# CATS-Vega-MCU.net
KiCad netlist of a schematic drawn in Altium Designer
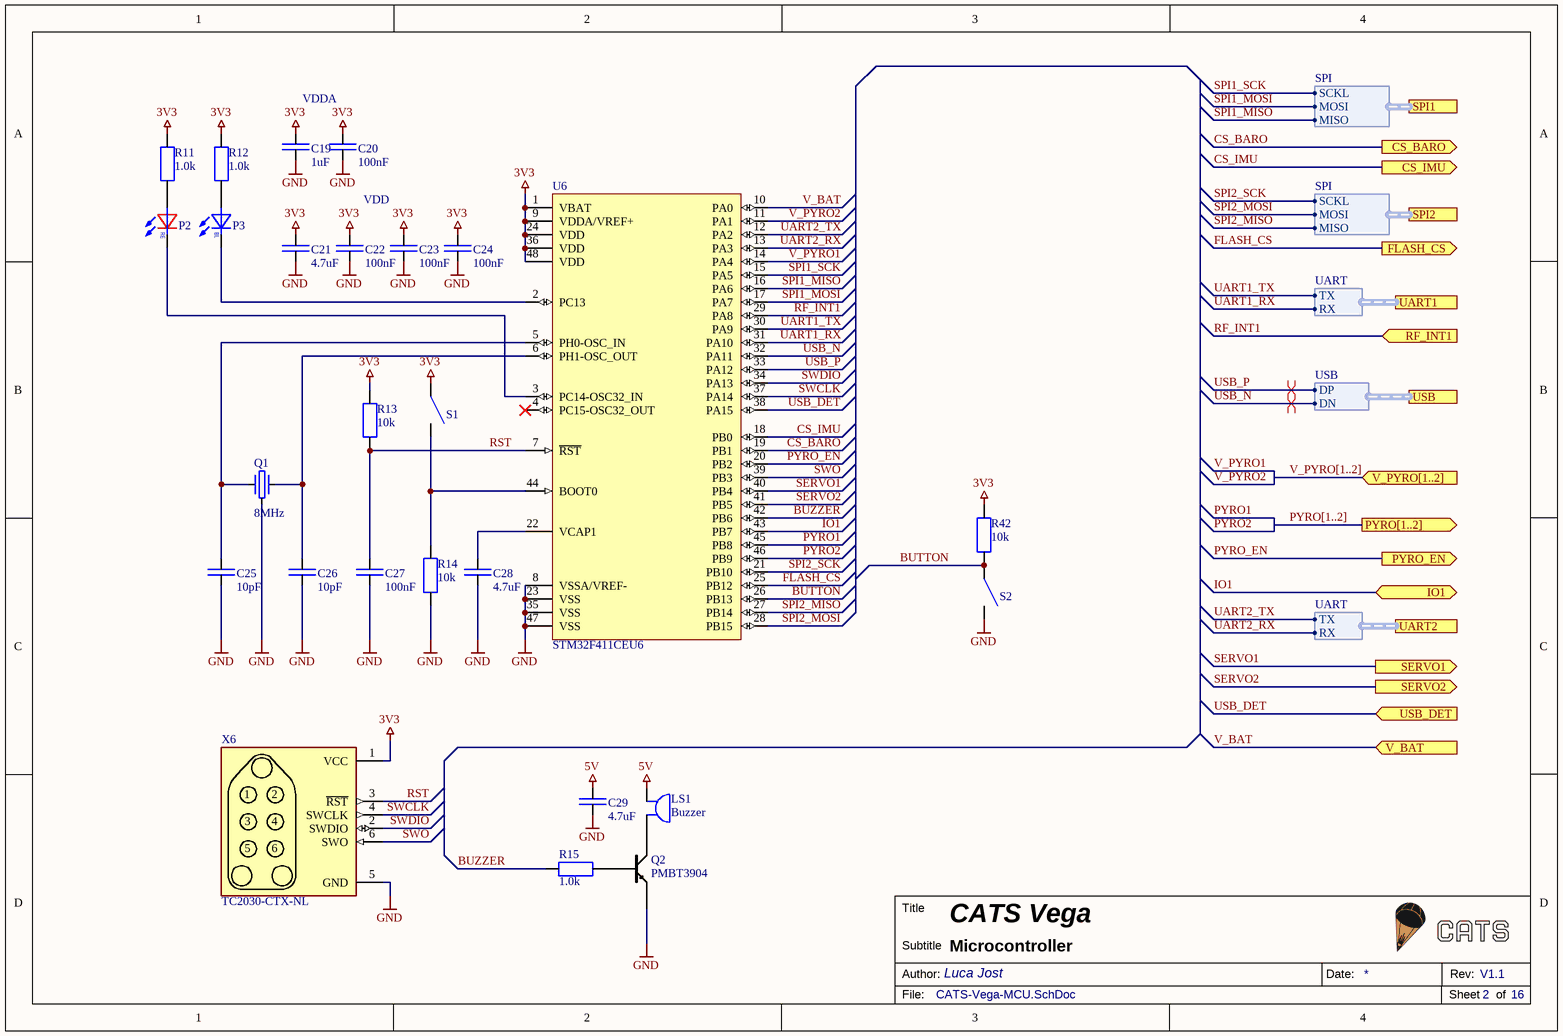
[diagram p0: CATS-Vega-MCU.SchDoc]

(export (version "E")
  (design (tool "Eeschema 10.0.6"))
  (components
    (comp (ref "C19")
      (value "1uF")
      (footprint "SMD Keramikkondensator 0603")
      (description "SMD Ceramic Capacitor E6")
      (libsource (lib "CATS-EUROC") (part "E6 - 1uF"))
    )
    (comp (ref "C20")
      (value "100nF")
      (footprint "SMD Keramikkondensator 0603")
      (description "SMD Ceramic Capacitor E6")
      (libsource (lib "CATS-EUROC") (part "E6 - 100nF"))
    )
    (comp (ref "C21")
      (value "4.7uF")
      (footprint "SMD Keramikkondensator 0603")
      (description "SMD Ceramic Capacitor E6")
      (libsource (lib "CATS-EUROC") (part "E6 - 4.7uF"))
    )
    (comp (ref "C22")
      (value "100nF")
      (footprint "SMD Keramikkondensator 0603")
      (description "SMD Ceramic Capacitor E6")
      (libsource (lib "CATS-EUROC") (part "E6 - 100nF"))
    )
    (comp (ref "C23")
      (value "100nF")
      (footprint "SMD Keramikkondensator 0603")
      (description "SMD Ceramic Capacitor E6")
      (libsource (lib "CATS-EUROC") (part "E6 - 100nF"))
    )
    (comp (ref "C24")
      (value "100nF")
      (footprint "SMD Keramikkondensator 0603")
      (description "SMD Ceramic Capacitor E6")
      (libsource (lib "CATS-EUROC") (part "E6 - 100nF"))
    )
    (comp (ref "C25")
      (value "10pF")
      (footprint "SMD Keramikkondensator 0603")
      (description "SMD Ceramic Capacitor E6")
      (libsource (lib "CATS-EUROC") (part "E6 - 10pF"))
    )
    (comp (ref "C26")
      (value "10pF")
      (footprint "SMD Keramikkondensator 0603")
      (description "SMD Ceramic Capacitor E6")
      (libsource (lib "CATS-EUROC") (part "E6 - 10pF"))
    )
    (comp (ref "C27")
      (value "100nF")
      (footprint "SMD Keramikkondensator 0603")
      (description "SMD Ceramic Capacitor E6")
      (libsource (lib "CATS-EUROC") (part "E6 - 100nF"))
    )
    (comp (ref "C28")
      (value "4.7uF")
      (footprint "SMD Keramikkondensator 0603")
      (description "SMD Ceramic Capacitor E6")
      (libsource (lib "CATS-EUROC") (part "E6 - 4.7uF"))
    )
    (comp (ref "C29")
      (value "4.7uF")
      (footprint "SMD Keramikkondensator 0603")
      (description "SMD Ceramic Capacitor E6")
      (libsource (lib "CATS-EUROC") (part "E6 - 4.7uF"))
    )
    (comp (ref "LS1")
      (value "Buzzer")
      (footprint "SMD BUZZER CMT-8504")
      (description "Buzzers Indicator, Internally Driven Piezo 12V 10mA 3kHz 100dB @ 12V, 10cm Through Hole PC Pins")
      (libsource (lib "Other") (part "Buzzer"))
    )
    (comp (ref "P2")
      (value "LED")
      (footprint "SMD LED 0603")
      (description "Color LED")
      (libsource (lib "") (part "LED_1"))
    )
    (comp (ref "P3")
      (value "LED")
      (footprint "SMD LED 0603")
      (description "Color LED")
      (libsource (lib "Diodes") (part "LED"))
    )
    (comp (ref "Q1")
      (value "8MHz")
      (footprint "SMD Crystal 3.2X2.5X0.8")
      (description "SMD Crystal Resonators 8MHz ±10ppm SMD,3.2x2.5mm")
      (libsource (lib "Other") (part "Crystal"))
    )
    (comp (ref "Q2")
      (value "PMBT3904")
      (footprint "SMD Transistor SOT-23")
      (description "40 V, 200 mA NPN switching transisto")
      (libsource (lib "Electronic Switches") (part "PMBT3904"))
    )
    (comp (ref "R11")
      (value "1.0k")
      (footprint "SMD Widerstand 0603")
      (description "SMD Chip Resistor E24")
      (libsource (lib "CATS-EUROC") (part "E24 - 1.0k"))
    )
    (comp (ref "R12")
      (value "1.0k")
      (footprint "SMD Widerstand 0603")
      (description "SMD Chip Resistor E24")
      (libsource (lib "CATS-EUROC") (part "E24 - 1.0k"))
    )
    (comp (ref "R13")
      (value "10k")
      (footprint "SMD Widerstand 0603")
      (description "SMD Chip Resistor E24")
      (libsource (lib "CATS-EUROC") (part "E24 - 10k"))
    )
    (comp (ref "R14")
      (value "10k")
      (footprint "SMD Widerstand 0603")
      (description "SMD Chip Resistor E24")
      (libsource (lib "CATS-EUROC") (part "E24 - 10k"))
    )
    (comp (ref "R15")
      (value "1.0k")
      (footprint "SMD Widerstand 0603")
      (description "SMD Chip Resistor E24")
      (libsource (lib "") (part "E24 - 1.0k_1"))
    )
    (comp (ref "R42")
      (value "10k")
      (footprint "SMD Widerstand 0603")
      (description "SMD Chip Resistor E24")
      (libsource (lib "CATS-EUROC") (part "E24 - 10k"))
    )
    (comp (ref "S1")
      (value "SMD-Button")
      (footprint "SMD Button 2.5x3x1.2")
      (description "Button SPST")
      (libsource (lib "CATS-EUROC") (part "Button 3mmx2.5mm"))
    )
    (comp (ref "S2")
      (value "SMD-Button")
      (footprint "SMD Button 2.5x3x1.2")
      (description "Button SPST")
      (libsource (lib "CATS-EUROC") (part "Button 3mmx2.5mm"))
    )
    (comp (ref "U6")
      (value "STM32F411CEU6")
      (footprint "SMD IC QFN-48")
      (description "ARM® Cortex®-M4 series Microcontroller IC 32-Bit 100MHz 512KB (512K x 8) FLASH 48-UFQFPN (7x7)")
      (libsource (lib "Microcontrollers") (part "STM32F411CEU6"))
    )
    (comp (ref "X6")
      (value "TC2030-CTX-NL")
      (footprint "SMD Connector TC2030")
      (description "Tag-Connect for ARM-Cortex (6-Pin)")
      (libsource (lib "Connectors") (part "TC2030-CTX-NL"))
    )
  )
  (nets
    (net (code "4") (name "/BUTTON") (class "Default")
      (node (ref "R42") (pin "1") (pinfunction "1_1") (pintype "passive"))
      (node (ref "S2") (pin "1") (pinfunction "1_1") (pintype "passive"))
      (node (ref "U6") (pin "26") (pinfunction "PB13_26") (pintype "bidirectional"))
    )
    (net (code "5") (name "/BUZZER") (class "Default")
      (node (ref "R15") (pin "2") (pinfunction "2_2") (pintype "passive"))
      (node (ref "U6") (pin "42") (pinfunction "PB6_42") (pintype "bidirectional"))
    )
    (net (code "6") (name "/CS_BARO") (class "Default")
      (node (ref "U6") (pin "19") (pinfunction "PB1_19") (pintype "bidirectional"))
    )
    (net (code "7") (name "/CS_IMU") (class "Default")
      (node (ref "U6") (pin "18") (pinfunction "PB0_18") (pintype "bidirectional"))
    )
    (net (code "8") (name "/FLASH_CS") (class "Default")
      (node (ref "U6") (pin "25") (pinfunction "PB12_25") (pintype "bidirectional"))
    )
    (net (code "9") (name "/IO1") (class "Default")
      (node (ref "U6") (pin "43") (pinfunction "PB7_43") (pintype "bidirectional"))
    )
    (net (code "10") (name "/PYRO1") (class "Default")
      (node (ref "U6") (pin "45") (pinfunction "PB8_45") (pintype "bidirectional"))
    )
    (net (code "11") (name "/PYRO2") (class "Default")
      (node (ref "U6") (pin "46") (pinfunction "PB9_46") (pintype "bidirectional"))
    )
    (net (code "13") (name "/PYRO_EN") (class "Default")
      (node (ref "U6") (pin "20") (pinfunction "PB2_20") (pintype "bidirectional"))
    )
    (net (code "14") (name "/RF_INT1") (class "Default")
      (node (ref "U6") (pin "29") (pinfunction "PA8_29") (pintype "bidirectional"))
    )
    (net (code "15") (name "/RST") (class "Default")
      (node (ref "C27") (pin "2") (pinfunction "2_2") (pintype "passive"))
      (node (ref "R13") (pin "1") (pinfunction "1_1") (pintype "passive"))
      (node (ref "U6") (pin "7") (pinfunction "~{RST}_7") (pintype "input"))
      (node (ref "X6") (pin "3") (pinfunction "~{RST}_3") (pintype "output"))
    )
    (net (code "16") (name "/SERVO1") (class "Default")
      (node (ref "U6") (pin "40") (pinfunction "PB4_40") (pintype "bidirectional"))
    )
    (net (code "17") (name "/SERVO2") (class "Default")
      (node (ref "U6") (pin "41") (pinfunction "PB5_41") (pintype "bidirectional"))
    )
    (net (code "18") (name "/SPI1_MISO") (class "Default")
      (node (ref "U6") (pin "16") (pinfunction "PA6_16") (pintype "bidirectional"))
    )
    (net (code "19") (name "/SPI1_MOSI") (class "Default")
      (node (ref "U6") (pin "17") (pinfunction "PA7_17") (pintype "bidirectional"))
    )
    (net (code "20") (name "/SPI1_SCK") (class "Default")
      (node (ref "U6") (pin "15") (pinfunction "PA5_15") (pintype "bidirectional"))
    )
    (net (code "21") (name "/SPI2_MISO") (class "Default")
      (node (ref "U6") (pin "27") (pinfunction "PB14_27") (pintype "bidirectional"))
    )
    (net (code "22") (name "/SPI2_MOSI") (class "Default")
      (node (ref "U6") (pin "28") (pinfunction "PB15_28") (pintype "bidirectional"))
    )
    (net (code "23") (name "/SPI2_SCK") (class "Default")
      (node (ref "U6") (pin "21") (pinfunction "PB10_21") (pintype "bidirectional"))
    )
    (net (code "24") (name "/SWCLK") (class "Default")
      (node (ref "U6") (pin "37") (pinfunction "PA14_37") (pintype "bidirectional"))
      (node (ref "X6") (pin "4") (pinfunction "SWCLK_4") (pintype "output"))
    )
    (net (code "25") (name "/SWDIO") (class "Default")
      (node (ref "U6") (pin "34") (pinfunction "PA13_34") (pintype "bidirectional"))
      (node (ref "X6") (pin "2") (pinfunction "SWDIO_2") (pintype "bidirectional"))
    )
    (net (code "26") (name "/SWO") (class "Default")
      (node (ref "U6") (pin "39") (pinfunction "PB3_39") (pintype "bidirectional"))
      (node (ref "X6") (pin "6") (pinfunction "SWO_6") (pintype "input"))
    )
    (net (code "27") (name "/UART1_RX") (class "Default")
      (node (ref "U6") (pin "31") (pinfunction "PA10_31") (pintype "bidirectional"))
    )
    (net (code "28") (name "/UART1_TX") (class "Default")
      (node (ref "U6") (pin "30") (pinfunction "PA9_30") (pintype "bidirectional"))
    )
    (net (code "29") (name "/UART2_RX") (class "Default")
      (node (ref "U6") (pin "13") (pinfunction "PA3_13") (pintype "bidirectional"))
    )
    (net (code "30") (name "/UART2_TX") (class "Default")
      (node (ref "U6") (pin "12") (pinfunction "PA2_12") (pintype "bidirectional"))
    )
    (net (code "31") (name "/USB_DET") (class "Default")
      (node (ref "U6") (pin "38") (pinfunction "PA15_38") (pintype "bidirectional"))
    )
    (net (code "32") (name "/USB_N") (class "Default")
      (node (ref "U6") (pin "32") (pinfunction "PA11_32") (pintype "bidirectional"))
    )
    (net (code "33") (name "/USB_P") (class "Default")
      (node (ref "U6") (pin "33") (pinfunction "PA12_33") (pintype "bidirectional"))
    )
    (net (code "34") (name "/V_BAT") (class "Default")
      (node (ref "U6") (pin "10") (pinfunction "PA0_10") (pintype "bidirectional"))
    )
    (net (code "35") (name "/V_PYRO1") (class "Default")
      (node (ref "U6") (pin "14") (pinfunction "PA4_14") (pintype "bidirectional"))
    )
    (net (code "36") (name "/V_PYRO2") (class "Default")
      (node (ref "U6") (pin "11") (pinfunction "PA1_11") (pintype "bidirectional"))
    )
    (net (code "41") (name "3V3") (class "Default")
      (node (ref "C19") (pin "2") (pinfunction "2_2") (pintype "passive"))
      (node (ref "C20") (pin "2") (pinfunction "2_2") (pintype "passive"))
      (node (ref "C21") (pin "2") (pinfunction "2_2") (pintype "passive"))
      (node (ref "C22") (pin "2") (pinfunction "2_2") (pintype "passive"))
      (node (ref "C23") (pin "2") (pinfunction "2_2") (pintype "passive"))
      (node (ref "C24") (pin "2") (pinfunction "2_2") (pintype "passive"))
      (node (ref "R11") (pin "2") (pinfunction "2_2") (pintype "passive"))
      (node (ref "R12") (pin "2") (pinfunction "2_2") (pintype "passive"))
      (node (ref "R13") (pin "2") (pinfunction "2_2") (pintype "passive"))
      (node (ref "R42") (pin "2") (pinfunction "2_2") (pintype "passive"))
      (node (ref "S1") (pin "1") (pinfunction "1_1") (pintype "passive"))
      (node (ref "U6") (pin "1") (pinfunction "VBAT_1") (pintype "passive"))
      (node (ref "U6") (pin "24") (pinfunction "VDD_24") (pintype "passive"))
      (node (ref "U6") (pin "36") (pinfunction "VDD_36") (pintype "passive"))
      (node (ref "U6") (pin "48") (pinfunction "VDD_48") (pintype "passive"))
      (node (ref "U6") (pin "9") (pinfunction "VDDA/VREF+_9") (pintype "passive"))
      (node (ref "X6") (pin "1") (pinfunction "VCC_1") (pintype "power_in"))
    )
    (net (code "42") (name "5V") (class "Default")
      (node (ref "C29") (pin "2") (pinfunction "2_2") (pintype "passive"))
      (node (ref "LS1") (pin "1") (pinfunction "1_1") (pintype "passive"))
    )
    (net (code "43") (name "GND") (class "Default")
      (node (ref "C19") (pin "1") (pinfunction "1_1") (pintype "passive"))
      (node (ref "C20") (pin "1") (pinfunction "1_1") (pintype "passive"))
      (node (ref "C21") (pin "1") (pinfunction "1_1") (pintype "passive"))
      (node (ref "C22") (pin "1") (pinfunction "1_1") (pintype "passive"))
      (node (ref "C23") (pin "1") (pinfunction "1_1") (pintype "passive"))
      (node (ref "C24") (pin "1") (pinfunction "1_1") (pintype "passive"))
      (node (ref "C25") (pin "1") (pinfunction "1_1") (pintype "passive"))
      (node (ref "C26") (pin "1") (pinfunction "1_1") (pintype "passive"))
      (node (ref "C27") (pin "1") (pinfunction "1_1") (pintype "passive"))
      (node (ref "C28") (pin "1") (pinfunction "1_1") (pintype "passive"))
      (node (ref "C29") (pin "1") (pinfunction "1_1") (pintype "passive"))
      (node (ref "Q1") (pin "3") (pinfunction "3_3") (pintype "power_in"))
      (node (ref "Q2") (pin "E") (pintype "passive"))
      (node (ref "R14") (pin "1") (pinfunction "1_1") (pintype "passive"))
      (node (ref "S2") (pin "2") (pinfunction "2_2") (pintype "passive"))
      (node (ref "U6") (pin "23") (pinfunction "VSS_23") (pintype "passive"))
      (node (ref "U6") (pin "35") (pinfunction "VSS_35") (pintype "passive"))
      (node (ref "U6") (pin "47") (pinfunction "VSS_47") (pintype "passive"))
      (node (ref "U6") (pin "8") (pinfunction "VSSA/VREF-_8") (pintype "passive"))
      (node (ref "X6") (pin "5") (pinfunction "GND_5") (pintype "power_in"))
    )
    (net (code "44") (name "Net-(LS1-Pad2)") (class "Default")
      (node (ref "LS1") (pin "2") (pinfunction "2_2") (pintype "passive"))
      (node (ref "Q2") (pin "C") (pintype "passive"))
    )
    (net (code "45") (name "Net-(P2-PadA)") (class "Default")
      (node (ref "P2") (pin "A") (pinfunction "A_A") (pintype "passive"))
      (node (ref "R11") (pin "1") (pinfunction "1_1") (pintype "passive"))
    )
    (net (code "46") (name "Net-(P3-PadA)") (class "Default")
      (node (ref "P3") (pin "A") (pinfunction "A_A") (pintype "passive"))
      (node (ref "R12") (pin "1") (pinfunction "1_1") (pintype "passive"))
    )
    (net (code "47") (name "Net-(Q2-PadB)") (class "Default")
      (node (ref "Q2") (pin "B") (pintype "passive"))
      (node (ref "R15") (pin "1") (pinfunction "1_1") (pintype "passive"))
    )
    (net (code "48") (name "Net-(U6-BOOT0)") (class "Default")
      (node (ref "R14") (pin "2") (pinfunction "2_2") (pintype "passive"))
      (node (ref "S1") (pin "2") (pinfunction "2_2") (pintype "passive"))
      (node (ref "U6") (pin "44") (pinfunction "BOOT0_44") (pintype "input"))
    )
    (net (code "49") (name "Net-(U6-PC13)") (class "Default")
      (node (ref "P3") (pin "K") (pinfunction "K_K") (pintype "passive"))
      (node (ref "U6") (pin "2") (pinfunction "PC13_2") (pintype "bidirectional"))
    )
    (net (code "50") (name "Net-(U6-PC14-OSC32_IN)") (class "Default")
      (node (ref "P2") (pin "K") (pinfunction "K_K") (pintype "passive"))
      (node (ref "U6") (pin "3") (pinfunction "PC14-OSC32_IN_3") (pintype "bidirectional"))
    )
    (net (code "51") (name "Net-(U6-PH0-OSC_IN)") (class "Default")
      (node (ref "C25") (pin "2") (pinfunction "2_2") (pintype "passive"))
      (node (ref "Q1") (pin "1") (pinfunction "1_1") (pintype "passive"))
      (node (ref "U6") (pin "5") (pinfunction "PH0-OSC_IN_5") (pintype "bidirectional"))
    )
    (net (code "52") (name "Net-(U6-PH1-OSC_OUT)") (class "Default")
      (node (ref "C26") (pin "2") (pinfunction "2_2") (pintype "passive"))
      (node (ref "Q1") (pin "2") (pinfunction "2_2") (pintype "passive"))
      (node (ref "U6") (pin "6") (pinfunction "PH1-OSC_OUT_6") (pintype "bidirectional"))
    )
    (net (code "53") (name "Net-(U6-VCAP1)") (class "Default")
      (node (ref "C28") (pin "2") (pinfunction "2_2") (pintype "passive"))
      (node (ref "U6") (pin "22") (pinfunction "VCAP1_22") (pintype "passive"))
    )
    (net (code "54") (name "unconnected-(U6-PC15-OSC32_OUT-Pad4)") (class "Default")
      (node (ref "U6") (pin "4") (pinfunction "PC15-OSC32_OUT_4") (pintype "bidirectional+no_connect"))
    )
  )
)
